# oled_i2c.net
KiCad netlist of a schematic drawn in EAGLE
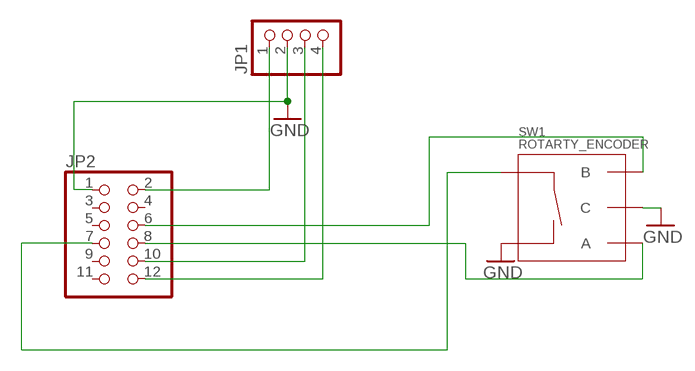
[diagram p0: schematic, sheet 1]

(export (version "E")
  (design (tool "Eeschema 10.0.6"))
  (components
    (comp (ref "JP1")
      (value "PINHD-1X4")
      (footprint "eagle-import:1X04")
      (libsource (lib "eagle-import") (part "PINHD-1X4"))
    )
    (comp (ref "JP2")
      (value "PINHD-2X6")
      (footprint "eagle-import:2X06")
      (libsource (lib "eagle-import") (part "PINHD-2X6"))
    )
    (comp (ref "SW1")
      (value "ROTARTY_ENCODER")
      (footprint "eagle-import:ROTARY_ENC_PLAIN")
      (libsource (lib "eagle-import") (part "ROTARTY_ENCODER"))
    )
  )
  (nets
    (net (code "1") (name "GND") (class "Default")
      (node (ref "JP1") (pin "2") (pinfunction "2_2") (pintype "passive"))
      (node (ref "JP2") (pin "1") (pinfunction "1_1") (pintype "passive"))
      (node (ref "SW1") (pin "C") (pinfunction "C_C") (pintype "bidirectional"))
      (node (ref "SW1") (pin "SW-") (pinfunction "SW-_SW-") (pintype "bidirectional"))
    )
    (net (code "2") (name "Net-(JP1-Pad1)") (class "Default")
      (node (ref "JP1") (pin "1") (pinfunction "1_1") (pintype "passive"))
      (node (ref "JP2") (pin "2") (pinfunction "2_2") (pintype "passive"))
    )
    (net (code "3") (name "Net-(JP1-Pad3)") (class "Default")
      (node (ref "JP1") (pin "3") (pinfunction "3_3") (pintype "passive"))
      (node (ref "JP2") (pin "10") (pinfunction "10_10") (pintype "passive"))
    )
    (net (code "4") (name "Net-(JP1-Pad4)") (class "Default")
      (node (ref "JP1") (pin "4") (pinfunction "4_4") (pintype "passive"))
      (node (ref "JP2") (pin "12") (pinfunction "12_12") (pintype "passive"))
    )
    (net (code "5") (name "Net-(JP2-Pad6)") (class "Default")
      (node (ref "JP2") (pin "6") (pinfunction "6_6") (pintype "passive"))
      (node (ref "SW1") (pin "B") (pinfunction "B_B") (pintype "bidirectional"))
    )
    (net (code "6") (name "Net-(JP2-Pad7)") (class "Default")
      (node (ref "JP2") (pin "7") (pinfunction "7_7") (pintype "passive"))
      (node (ref "SW1") (pin "SW+") (pinfunction "SW+_SW+") (pintype "bidirectional"))
    )
    (net (code "7") (name "Net-(JP2-Pad8)") (class "Default")
      (node (ref "JP2") (pin "8") (pinfunction "8_8") (pintype "passive"))
      (node (ref "SW1") (pin "A") (pinfunction "A_A") (pintype "bidirectional"))
    )
    (net (code "8") (name "unconnected-(JP2-Pad3)") (class "Default")
      (node (ref "JP2") (pin "3") (pinfunction "3_3") (pintype "passive"))
    )
    (net (code "9") (name "unconnected-(JP2-Pad4)") (class "Default")
      (node (ref "JP2") (pin "4") (pinfunction "4_4") (pintype "passive"))
    )
    (net (code "10") (name "unconnected-(JP2-Pad5)") (class "Default")
      (node (ref "JP2") (pin "5") (pinfunction "5_5") (pintype "passive"))
    )
    (net (code "11") (name "unconnected-(JP2-Pad9)") (class "Default")
      (node (ref "JP2") (pin "9") (pinfunction "9_9") (pintype "passive"))
    )
    (net (code "12") (name "unconnected-(JP2-Pad11)") (class "Default")
      (node (ref "JP2") (pin "11") (pinfunction "11_11") (pintype "passive"))
    )
  )
)
